# Airgap.net
KiCad netlist of a schematic drawn in EAGLE
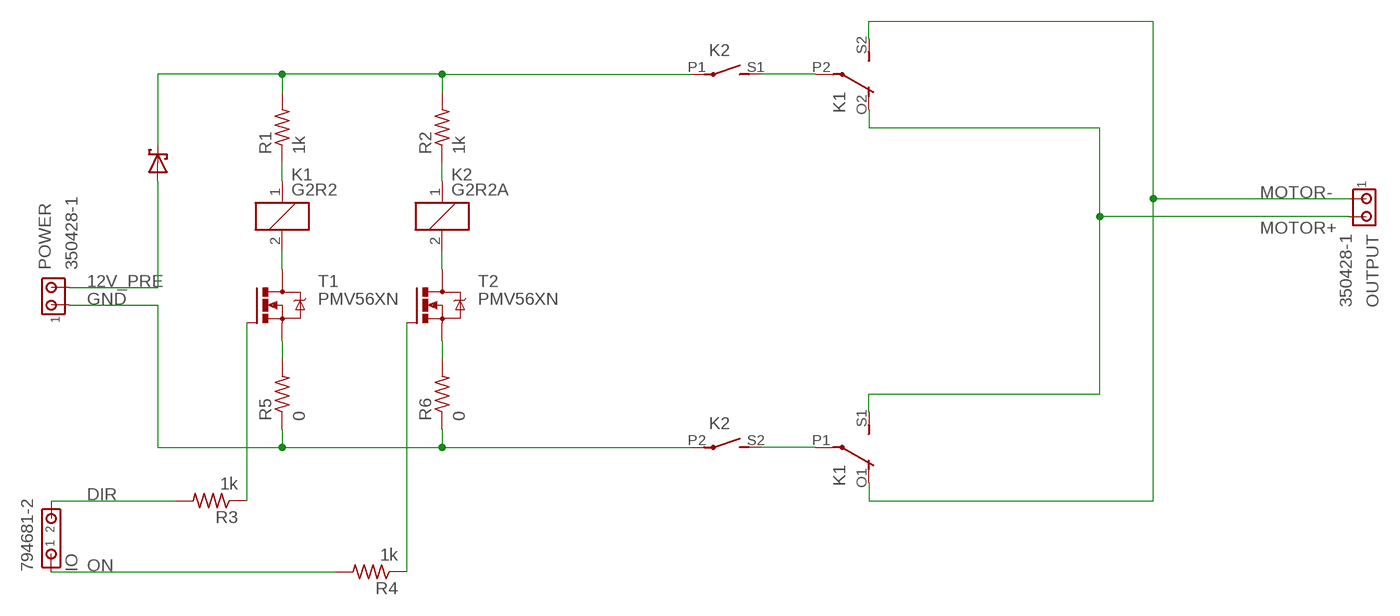
[diagram p0: schematic, sheet 1]

(export (version "E")
  (design (tool "Eeschema 10.0.6"))
  (components
    (comp (ref "D3")
      (value "6A4")
      (footprint "eagle-import:P6T15")
      (libsource (lib "eagle-import") (part "5KPXX"))
    )
    (comp (ref "IO")
      (value "794681-2")
      (footprint "eagle-import:794681-2")
      (libsource (lib "eagle-import") (part "794681-2"))
    )
    (comp (ref "K1")
      (value "G2R2")
      (footprint "eagle-import:G2R2")
      (fields (field (name "MF") "OMRON COMPONENTS USA") (field (name "MPN") "G2R-2-DC6"))
      (libsource (lib "eagle-import") (part "G2R2"))
    )
    (comp (ref "K2")
      (value "G2R2A")
      (footprint "eagle-import:G2R2A")
      (fields (field (name "MPN") "G2R-2A-DC24"))
      (libsource (lib "eagle-import") (part "G2R2A"))
    )
    (comp (ref "OUTPUT")
      (value "350428-1")
      (footprint "eagle-import:350428-1")
      (libsource (lib "eagle-import") (part "350428-1"))
    )
    (comp (ref "POWER")
      (value "350428-1")
      (footprint "eagle-import:350428-1")
      (libsource (lib "eagle-import") (part "350428-1"))
    )
    (comp (ref "R1")
      (value "1k")
      (footprint "eagle-import:R1206")
      (fields (field (name "PART_NUM") "CR1206-FX-1001GLF"))
      (libsource (lib "eagle-import") (part "RESISTORSMD1206"))
    )
    (comp (ref "R2")
      (value "1k")
      (footprint "eagle-import:R1206")
      (fields (field (name "PART_NUM") "CR1206-FX-1001GLF"))
      (libsource (lib "eagle-import") (part "RESISTORSMD1206"))
    )
    (comp (ref "R3")
      (value "1k")
      (footprint "eagle-import:R1206")
      (fields (field (name "PART_NUM") "CR1206-FX-1001GLF"))
      (libsource (lib "eagle-import") (part "RESISTORSMD1206"))
    )
    (comp (ref "R4")
      (value "1k")
      (footprint "eagle-import:R1206")
      (fields (field (name "PART_NUM") "CR1206-FX-1001GLF"))
      (libsource (lib "eagle-import") (part "RESISTORSMD1206"))
    )
    (comp (ref "R5")
      (value "0")
      (footprint "eagle-import:R1206")
      (fields (field (name "PART_NUM") "CR1206-J/-000ELF"))
      (libsource (lib "eagle-import") (part "RESISTORSMD1206"))
    )
    (comp (ref "R6")
      (value "0")
      (footprint "eagle-import:R1206")
      (fields (field (name "PART_NUM") "CR1206-J/-000ELF"))
      (libsource (lib "eagle-import") (part "RESISTORSMD1206"))
    )
    (comp (ref "T1")
      (value "PMV56XN")
      (footprint "eagle-import:SOT23")
      (fields (field (name "PART_NUM") "PMV56XN,215"))
      (libsource (lib "eagle-import") (part "N-CHANNEL_MOSFETPMV56XN,215"))
    )
    (comp (ref "T2")
      (value "PMV56XN")
      (footprint "eagle-import:SOT23")
      (fields (field (name "PART_NUM") "PMV56XN,215"))
      (libsource (lib "eagle-import") (part "N-CHANNEL_MOSFETPMV56XN,215"))
    )
  )
  (nets
    (net (code "1") (name "/12V_PRE") (class "Default")
      (node (ref "D3") (pin "A") (pinfunction "A_A") (pintype "passive"))
      (node (ref "POWER") (pin "2") (pinfunction "2_2") (pintype "passive"))
    )
    (net (code "2") (name "/DIR") (class "Default")
      (node (ref "IO") (pin "2") (pinfunction "2_2") (pintype "passive"))
      (node (ref "R3") (pin "2") (pinfunction "2_2") (pintype "passive"))
    )
    (net (code "3") (name "/GND") (class "Default")
      (node (ref "K2") (pin "P2") (pinfunction "P_P2") (pintype "passive"))
      (node (ref "POWER") (pin "1") (pinfunction "1_1") (pintype "passive"))
      (node (ref "R5") (pin "1") (pinfunction "1_1") (pintype "passive"))
      (node (ref "R6") (pin "1") (pinfunction "1_1") (pintype "passive"))
    )
    (net (code "4") (name "/MOTOR+") (class "Default")
      (node (ref "K1") (pin "O2") (pinfunction "O_O2") (pintype "passive"))
      (node (ref "K1") (pin "S1") (pinfunction "S_S1") (pintype "passive"))
      (node (ref "OUTPUT") (pin "2") (pinfunction "2_2") (pintype "passive"))
    )
    (net (code "5") (name "/MOTOR-") (class "Default")
      (node (ref "K1") (pin "O1") (pinfunction "O_O1") (pintype "passive"))
      (node (ref "K1") (pin "S2") (pinfunction "S_S2") (pintype "passive"))
      (node (ref "OUTPUT") (pin "1") (pinfunction "1_1") (pintype "passive"))
    )
    (net (code "6") (name "/ON") (class "Default")
      (node (ref "IO") (pin "1") (pinfunction "1_1") (pintype "passive"))
      (node (ref "R4") (pin "2") (pinfunction "2_2") (pintype "passive"))
    )
    (net (code "7") (name "Net-(K1-Pad1)") (class "Default")
      (node (ref "K1") (pin "1") (pinfunction "1_1") (pintype "passive"))
      (node (ref "R1") (pin "1") (pinfunction "1_1") (pintype "passive"))
    )
    (net (code "8") (name "Net-(K1B-P)") (class "Default")
      (node (ref "K1") (pin "P1") (pinfunction "P_P1") (pintype "passive"))
      (node (ref "K2") (pin "S2") (pinfunction "S_S2") (pintype "passive"))
    )
    (net (code "9") (name "Net-(K1C-P)") (class "Default")
      (node (ref "K1") (pin "P2") (pinfunction "P_P2") (pintype "passive"))
      (node (ref "K2") (pin "S1") (pinfunction "S_S1") (pintype "passive"))
    )
    (net (code "10") (name "Net-(K2-Pad1)") (class "Default")
      (node (ref "K2") (pin "1") (pinfunction "1_1") (pintype "passive"))
      (node (ref "R2") (pin "1") (pinfunction "1_1") (pintype "passive"))
    )
    (net (code "11") (name "Net-(K2B-P)") (class "Default")
      (node (ref "D3") (pin "C") (pinfunction "C_C") (pintype "passive"))
      (node (ref "K2") (pin "P1") (pinfunction "P_P1") (pintype "passive"))
      (node (ref "R1") (pin "2") (pinfunction "2_2") (pintype "passive"))
      (node (ref "R2") (pin "2") (pinfunction "2_2") (pintype "passive"))
    )
    (net (code "12") (name "Net-(T1-D)") (class "Default")
      (node (ref "K1") (pin "2") (pinfunction "2_2") (pintype "passive"))
      (node (ref "T1") (pin "3") (pinfunction "D_3") (pintype "passive"))
    )
    (net (code "13") (name "Net-(T1-G)") (class "Default")
      (node (ref "R3") (pin "1") (pinfunction "1_1") (pintype "passive"))
      (node (ref "T1") (pin "1") (pinfunction "G_1") (pintype "passive"))
    )
    (net (code "14") (name "Net-(T1-S)") (class "Default")
      (node (ref "R5") (pin "2") (pinfunction "2_2") (pintype "passive"))
      (node (ref "T1") (pin "2") (pinfunction "S_2") (pintype "passive"))
    )
    (net (code "15") (name "Net-(T2-D)") (class "Default")
      (node (ref "K2") (pin "2") (pinfunction "2_2") (pintype "passive"))
      (node (ref "T2") (pin "3") (pinfunction "D_3") (pintype "passive"))
    )
    (net (code "16") (name "Net-(T2-G)") (class "Default")
      (node (ref "R4") (pin "1") (pinfunction "1_1") (pintype "passive"))
      (node (ref "T2") (pin "1") (pinfunction "G_1") (pintype "passive"))
    )
    (net (code "17") (name "Net-(T2-S)") (class "Default")
      (node (ref "R6") (pin "2") (pinfunction "2_2") (pintype "passive"))
      (node (ref "T2") (pin "2") (pinfunction "S_2") (pintype "passive"))
    )
  )
)
